# ESD.net
KiCad netlist of a schematic drawn in Altium Designer
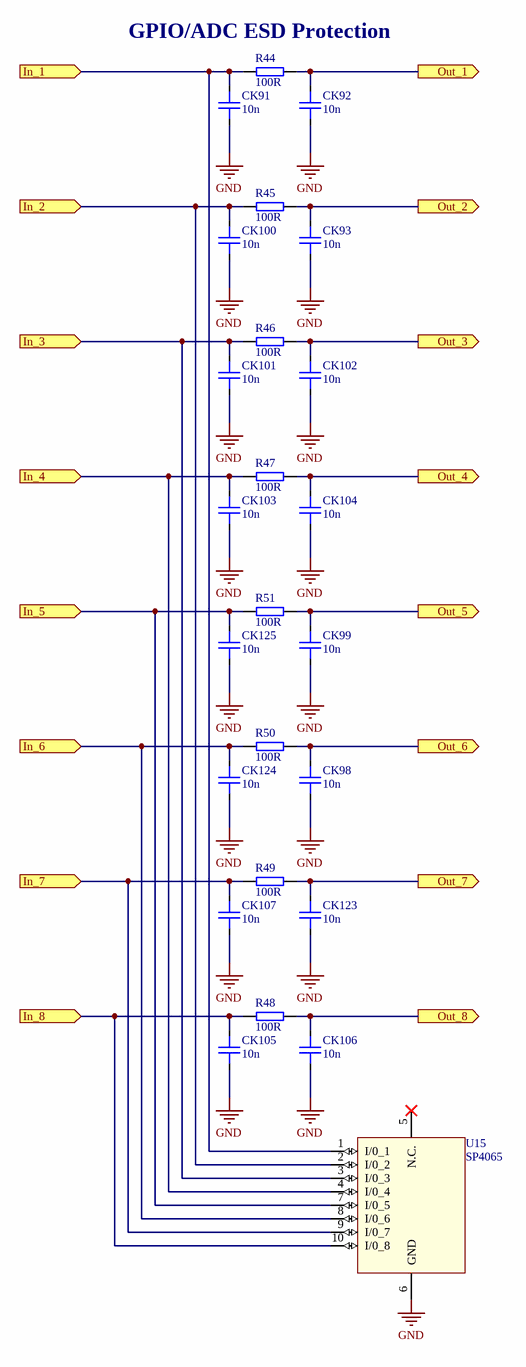
[diagram p0: ESD.SchDoc]

(export (version "E")
  (design (tool "Eeschema 10.0.6"))
  (components
    (comp (ref "CK91")
      (value "10n")
      (footprint "CAPC1608X09N(SMC0603)")
      (description "MLCC")
      (fields
        (field (name "TOLERANCE") "10%")
        (field (name "VOLTAGE") "50V")
        (field (name "AUTHOR") "JP/27.03.2014")
      )
      (libsource (lib "JP_C") (part "10n-50V-0603-X7R"))
    )
    (comp (ref "CK92")
      (value "10n")
      (footprint "CAPC1608X09N(SMC0603)")
      (description "MLCC")
      (fields
        (field (name "TOLERANCE") "10%")
        (field (name "VOLTAGE") "50V")
        (field (name "AUTHOR") "JP/27.03.2014")
      )
      (libsource (lib "JP_C") (part "10n-50V-0603-X7R"))
    )
    (comp (ref "CK93")
      (value "10n")
      (footprint "CAPC1608X09N(SMC0603)")
      (description "MLCC")
      (fields
        (field (name "TOLERANCE") "10%")
        (field (name "VOLTAGE") "50V")
        (field (name "AUTHOR") "JP/27.03.2014")
      )
      (libsource (lib "JP_C") (part "10n-50V-0603-X7R"))
    )
    (comp (ref "CK98")
      (value "10n")
      (footprint "CAPC1608X09N(SMC0603)")
      (description "MLCC")
      (fields
        (field (name "TOLERANCE") "10%")
        (field (name "VOLTAGE") "50V")
        (field (name "AUTHOR") "JP/27.03.2014")
      )
      (libsource (lib "JP_C") (part "10n-50V-0603-X7R"))
    )
    (comp (ref "CK99")
      (value "10n")
      (footprint "CAPC1608X09N(SMC0603)")
      (description "MLCC")
      (fields
        (field (name "TOLERANCE") "10%")
        (field (name "VOLTAGE") "50V")
        (field (name "AUTHOR") "JP/27.03.2014")
      )
      (libsource (lib "JP_C") (part "10n-50V-0603-X7R"))
    )
    (comp (ref "CK100")
      (value "10n")
      (footprint "CAPC1608X09N(SMC0603)")
      (description "MLCC")
      (fields
        (field (name "TOLERANCE") "10%")
        (field (name "VOLTAGE") "50V")
        (field (name "AUTHOR") "JP/27.03.2014")
      )
      (libsource (lib "JP_C") (part "10n-50V-0603-X7R"))
    )
    (comp (ref "CK101")
      (value "10n")
      (footprint "CAPC1608X09N(SMC0603)")
      (description "MLCC")
      (fields
        (field (name "TOLERANCE") "10%")
        (field (name "VOLTAGE") "50V")
        (field (name "AUTHOR") "JP/27.03.2014")
      )
      (libsource (lib "JP_C") (part "10n-50V-0603-X7R"))
    )
    (comp (ref "CK102")
      (value "10n")
      (footprint "CAPC1608X09N(SMC0603)")
      (description "MLCC")
      (fields
        (field (name "TOLERANCE") "10%")
        (field (name "VOLTAGE") "50V")
        (field (name "AUTHOR") "JP/27.03.2014")
      )
      (libsource (lib "JP_C") (part "10n-50V-0603-X7R"))
    )
    (comp (ref "CK103")
      (value "10n")
      (footprint "CAPC1608X09N(SMC0603)")
      (description "MLCC")
      (fields
        (field (name "TOLERANCE") "10%")
        (field (name "VOLTAGE") "50V")
        (field (name "AUTHOR") "JP/27.03.2014")
      )
      (libsource (lib "JP_C") (part "10n-50V-0603-X7R"))
    )
    (comp (ref "CK104")
      (value "10n")
      (footprint "CAPC1608X09N(SMC0603)")
      (description "MLCC")
      (fields
        (field (name "TOLERANCE") "10%")
        (field (name "VOLTAGE") "50V")
        (field (name "AUTHOR") "JP/27.03.2014")
      )
      (libsource (lib "JP_C") (part "10n-50V-0603-X7R"))
    )
    (comp (ref "CK105")
      (value "10n")
      (footprint "CAPC1608X09N(SMC0603)")
      (description "MLCC")
      (fields
        (field (name "TOLERANCE") "10%")
        (field (name "VOLTAGE") "50V")
        (field (name "AUTHOR") "JP/27.03.2014")
      )
      (libsource (lib "JP_C") (part "10n-50V-0603-X7R"))
    )
    (comp (ref "CK106")
      (value "10n")
      (footprint "CAPC1608X09N(SMC0603)")
      (description "MLCC")
      (fields
        (field (name "TOLERANCE") "10%")
        (field (name "VOLTAGE") "50V")
        (field (name "AUTHOR") "JP/27.03.2014")
      )
      (libsource (lib "JP_C") (part "10n-50V-0603-X7R"))
    )
    (comp (ref "CK107")
      (value "10n")
      (footprint "CAPC1608X09N(SMC0603)")
      (description "MLCC")
      (fields
        (field (name "TOLERANCE") "10%")
        (field (name "VOLTAGE") "50V")
        (field (name "AUTHOR") "JP/27.03.2014")
      )
      (libsource (lib "JP_C") (part "10n-50V-0603-X7R"))
    )
    (comp (ref "CK123")
      (value "10n")
      (footprint "CAPC1608X09N(SMC0603)")
      (description "MLCC")
      (fields
        (field (name "TOLERANCE") "10%")
        (field (name "VOLTAGE") "50V")
        (field (name "AUTHOR") "JP/27.03.2014")
      )
      (libsource (lib "JP_C") (part "10n-50V-0603-X7R"))
    )
    (comp (ref "CK124")
      (value "10n")
      (footprint "CAPC1608X09N(SMC0603)")
      (description "MLCC")
      (fields
        (field (name "TOLERANCE") "10%")
        (field (name "VOLTAGE") "50V")
        (field (name "AUTHOR") "JP/27.03.2014")
      )
      (libsource (lib "JP_C") (part "10n-50V-0603-X7R"))
    )
    (comp (ref "CK125")
      (value "10n")
      (footprint "CAPC1608X09N(SMC0603)")
      (description "MLCC")
      (fields
        (field (name "TOLERANCE") "10%")
        (field (name "VOLTAGE") "50V")
        (field (name "AUTHOR") "JP/27.03.2014")
      )
      (libsource (lib "JP_C") (part "10n-50V-0603-X7R"))
    )
    (comp (ref "R44")
      (value "100R")
      (footprint "RESC1608X06N(SMR0603)")
      (description "Chip Resistor")
      (fields (field (name "AUTHOR") "JP/10.06.2014"))
      (libsource (lib "JP_R") (part "100R-100mW-0603-ThickFilm"))
    )
    (comp (ref "R45")
      (value "100R")
      (footprint "RESC1608X06N(SMR0603)")
      (description "Chip Resistor")
      (fields (field (name "AUTHOR") "JP/10.06.2014"))
      (libsource (lib "JP_R") (part "100R-100mW-0603-ThickFilm"))
    )
    (comp (ref "R46")
      (value "100R")
      (footprint "RESC1608X06N(SMR0603)")
      (description "Chip Resistor")
      (fields (field (name "AUTHOR") "JP/10.06.2014"))
      (libsource (lib "JP_R") (part "100R-100mW-0603-ThickFilm"))
    )
    (comp (ref "R47")
      (value "100R")
      (footprint "RESC1608X06N(SMR0603)")
      (description "Chip Resistor")
      (fields (field (name "AUTHOR") "JP/10.06.2014"))
      (libsource (lib "JP_R") (part "100R-100mW-0603-ThickFilm"))
    )
    (comp (ref "R48")
      (value "100R")
      (footprint "RESC1608X06N(SMR0603)")
      (description "Chip Resistor")
      (fields (field (name "AUTHOR") "JP/10.06.2014"))
      (libsource (lib "JP_R") (part "100R-100mW-0603-ThickFilm"))
    )
    (comp (ref "R49")
      (value "100R")
      (footprint "RESC1608X06N(SMR0603)")
      (description "Chip Resistor")
      (fields (field (name "AUTHOR") "JP/10.06.2014"))
      (libsource (lib "JP_R") (part "100R-100mW-0603-ThickFilm"))
    )
    (comp (ref "R50")
      (value "100R")
      (footprint "RESC1608X06N(SMR0603)")
      (description "Chip Resistor")
      (fields (field (name "AUTHOR") "JP/10.06.2014"))
      (libsource (lib "JP_R") (part "100R-100mW-0603-ThickFilm"))
    )
    (comp (ref "R51")
      (value "100R")
      (footprint "RESC1608X06N(SMR0603)")
      (description "Chip Resistor")
      (fields (field (name "AUTHOR") "JP/10.06.2014"))
      (libsource (lib "JP_R") (part "100R-100mW-0603-ThickFilm"))
    )
    (comp (ref "U15")
      (value "SP4065")
      (footprint "TSSOP50P490X110-10N(MSOP10)")
      (description "3.3V 20A  Diode  ESD Array")
      (libsource (lib "JP_IC") (part "SP4065"))
    )
  )
  (nets
    (net (code "1") (name "/In_1") (class "Default")
      (node (ref "CK91") (pin "1") (pinfunction "1_1") (pintype "passive"))
      (node (ref "R44") (pin "1") (pinfunction "1_1") (pintype "passive"))
      (node (ref "U15") (pin "1") (pinfunction "I/0_1_1") (pintype "bidirectional"))
    )
    (net (code "2") (name "/In_2") (class "Default")
      (node (ref "CK100") (pin "1") (pinfunction "1_1") (pintype "passive"))
      (node (ref "R45") (pin "1") (pinfunction "1_1") (pintype "passive"))
      (node (ref "U15") (pin "2") (pinfunction "I/0_2_2") (pintype "bidirectional"))
    )
    (net (code "3") (name "/In_3") (class "Default")
      (node (ref "CK101") (pin "1") (pinfunction "1_1") (pintype "passive"))
      (node (ref "R46") (pin "1") (pinfunction "1_1") (pintype "passive"))
      (node (ref "U15") (pin "3") (pinfunction "I/0_3_3") (pintype "bidirectional"))
    )
    (net (code "4") (name "/In_4") (class "Default")
      (node (ref "CK103") (pin "1") (pinfunction "1_1") (pintype "passive"))
      (node (ref "R47") (pin "1") (pinfunction "1_1") (pintype "passive"))
      (node (ref "U15") (pin "4") (pinfunction "I/0_4_4") (pintype "bidirectional"))
    )
    (net (code "5") (name "/In_5") (class "Default")
      (node (ref "CK125") (pin "1") (pinfunction "1_1") (pintype "passive"))
      (node (ref "R51") (pin "1") (pinfunction "1_1") (pintype "passive"))
      (node (ref "U15") (pin "7") (pinfunction "I/0_5_7") (pintype "bidirectional"))
    )
    (net (code "6") (name "/In_6") (class "Default")
      (node (ref "CK124") (pin "1") (pinfunction "1_1") (pintype "passive"))
      (node (ref "R50") (pin "1") (pinfunction "1_1") (pintype "passive"))
      (node (ref "U15") (pin "8") (pinfunction "I/0_6_8") (pintype "bidirectional"))
    )
    (net (code "7") (name "/In_7") (class "Default")
      (node (ref "CK107") (pin "1") (pinfunction "1_1") (pintype "passive"))
      (node (ref "R49") (pin "1") (pinfunction "1_1") (pintype "passive"))
      (node (ref "U15") (pin "9") (pinfunction "I/0_7_9") (pintype "bidirectional"))
    )
    (net (code "8") (name "/In_8") (class "Default")
      (node (ref "CK105") (pin "1") (pinfunction "1_1") (pintype "passive"))
      (node (ref "R48") (pin "1") (pinfunction "1_1") (pintype "passive"))
      (node (ref "U15") (pin "10") (pinfunction "I/0_8_10") (pintype "bidirectional"))
    )
    (net (code "9") (name "/Out_1") (class "Default")
      (node (ref "CK92") (pin "1") (pinfunction "1_1") (pintype "passive"))
      (node (ref "R44") (pin "2") (pinfunction "2_2") (pintype "passive"))
    )
    (net (code "10") (name "/Out_2") (class "Default")
      (node (ref "CK93") (pin "1") (pinfunction "1_1") (pintype "passive"))
      (node (ref "R45") (pin "2") (pinfunction "2_2") (pintype "passive"))
    )
    (net (code "11") (name "/Out_3") (class "Default")
      (node (ref "CK102") (pin "1") (pinfunction "1_1") (pintype "passive"))
      (node (ref "R46") (pin "2") (pinfunction "2_2") (pintype "passive"))
    )
    (net (code "12") (name "/Out_4") (class "Default")
      (node (ref "CK104") (pin "1") (pinfunction "1_1") (pintype "passive"))
      (node (ref "R47") (pin "2") (pinfunction "2_2") (pintype "passive"))
    )
    (net (code "13") (name "/Out_5") (class "Default")
      (node (ref "CK99") (pin "1") (pinfunction "1_1") (pintype "passive"))
      (node (ref "R51") (pin "2") (pinfunction "2_2") (pintype "passive"))
    )
    (net (code "14") (name "/Out_6") (class "Default")
      (node (ref "CK98") (pin "1") (pinfunction "1_1") (pintype "passive"))
      (node (ref "R50") (pin "2") (pinfunction "2_2") (pintype "passive"))
    )
    (net (code "15") (name "/Out_7") (class "Default")
      (node (ref "CK123") (pin "1") (pinfunction "1_1") (pintype "passive"))
      (node (ref "R49") (pin "2") (pinfunction "2_2") (pintype "passive"))
    )
    (net (code "16") (name "/Out_8") (class "Default")
      (node (ref "CK106") (pin "1") (pinfunction "1_1") (pintype "passive"))
      (node (ref "R48") (pin "2") (pinfunction "2_2") (pintype "passive"))
    )
    (net (code "17") (name "GND") (class "Default")
      (node (ref "CK100") (pin "2") (pinfunction "2_2") (pintype "passive"))
      (node (ref "CK101") (pin "2") (pinfunction "2_2") (pintype "passive"))
      (node (ref "CK102") (pin "2") (pinfunction "2_2") (pintype "passive"))
      (node (ref "CK103") (pin "2") (pinfunction "2_2") (pintype "passive"))
      (node (ref "CK104") (pin "2") (pinfunction "2_2") (pintype "passive"))
      (node (ref "CK105") (pin "2") (pinfunction "2_2") (pintype "passive"))
      (node (ref "CK106") (pin "2") (pinfunction "2_2") (pintype "passive"))
      (node (ref "CK107") (pin "2") (pinfunction "2_2") (pintype "passive"))
      (node (ref "CK123") (pin "2") (pinfunction "2_2") (pintype "passive"))
      (node (ref "CK124") (pin "2") (pinfunction "2_2") (pintype "passive"))
      (node (ref "CK125") (pin "2") (pinfunction "2_2") (pintype "passive"))
      (node (ref "CK91") (pin "2") (pinfunction "2_2") (pintype "passive"))
      (node (ref "CK92") (pin "2") (pinfunction "2_2") (pintype "passive"))
      (node (ref "CK93") (pin "2") (pinfunction "2_2") (pintype "passive"))
      (node (ref "CK98") (pin "2") (pinfunction "2_2") (pintype "passive"))
      (node (ref "CK99") (pin "2") (pinfunction "2_2") (pintype "passive"))
      (node (ref "U15") (pin "6") (pinfunction "GND_6") (pintype "power_in"))
    )
    (net (code "18") (name "unconnected-(U15-N.C.-Pad5)") (class "Default")
      (node (ref "U15") (pin "5") (pinfunction "N.C._5") (pintype "power_in+no_connect"))
    )
  )
)
